# ECE411_Project1.net
KiCad netlist of a schematic drawn in EAGLE
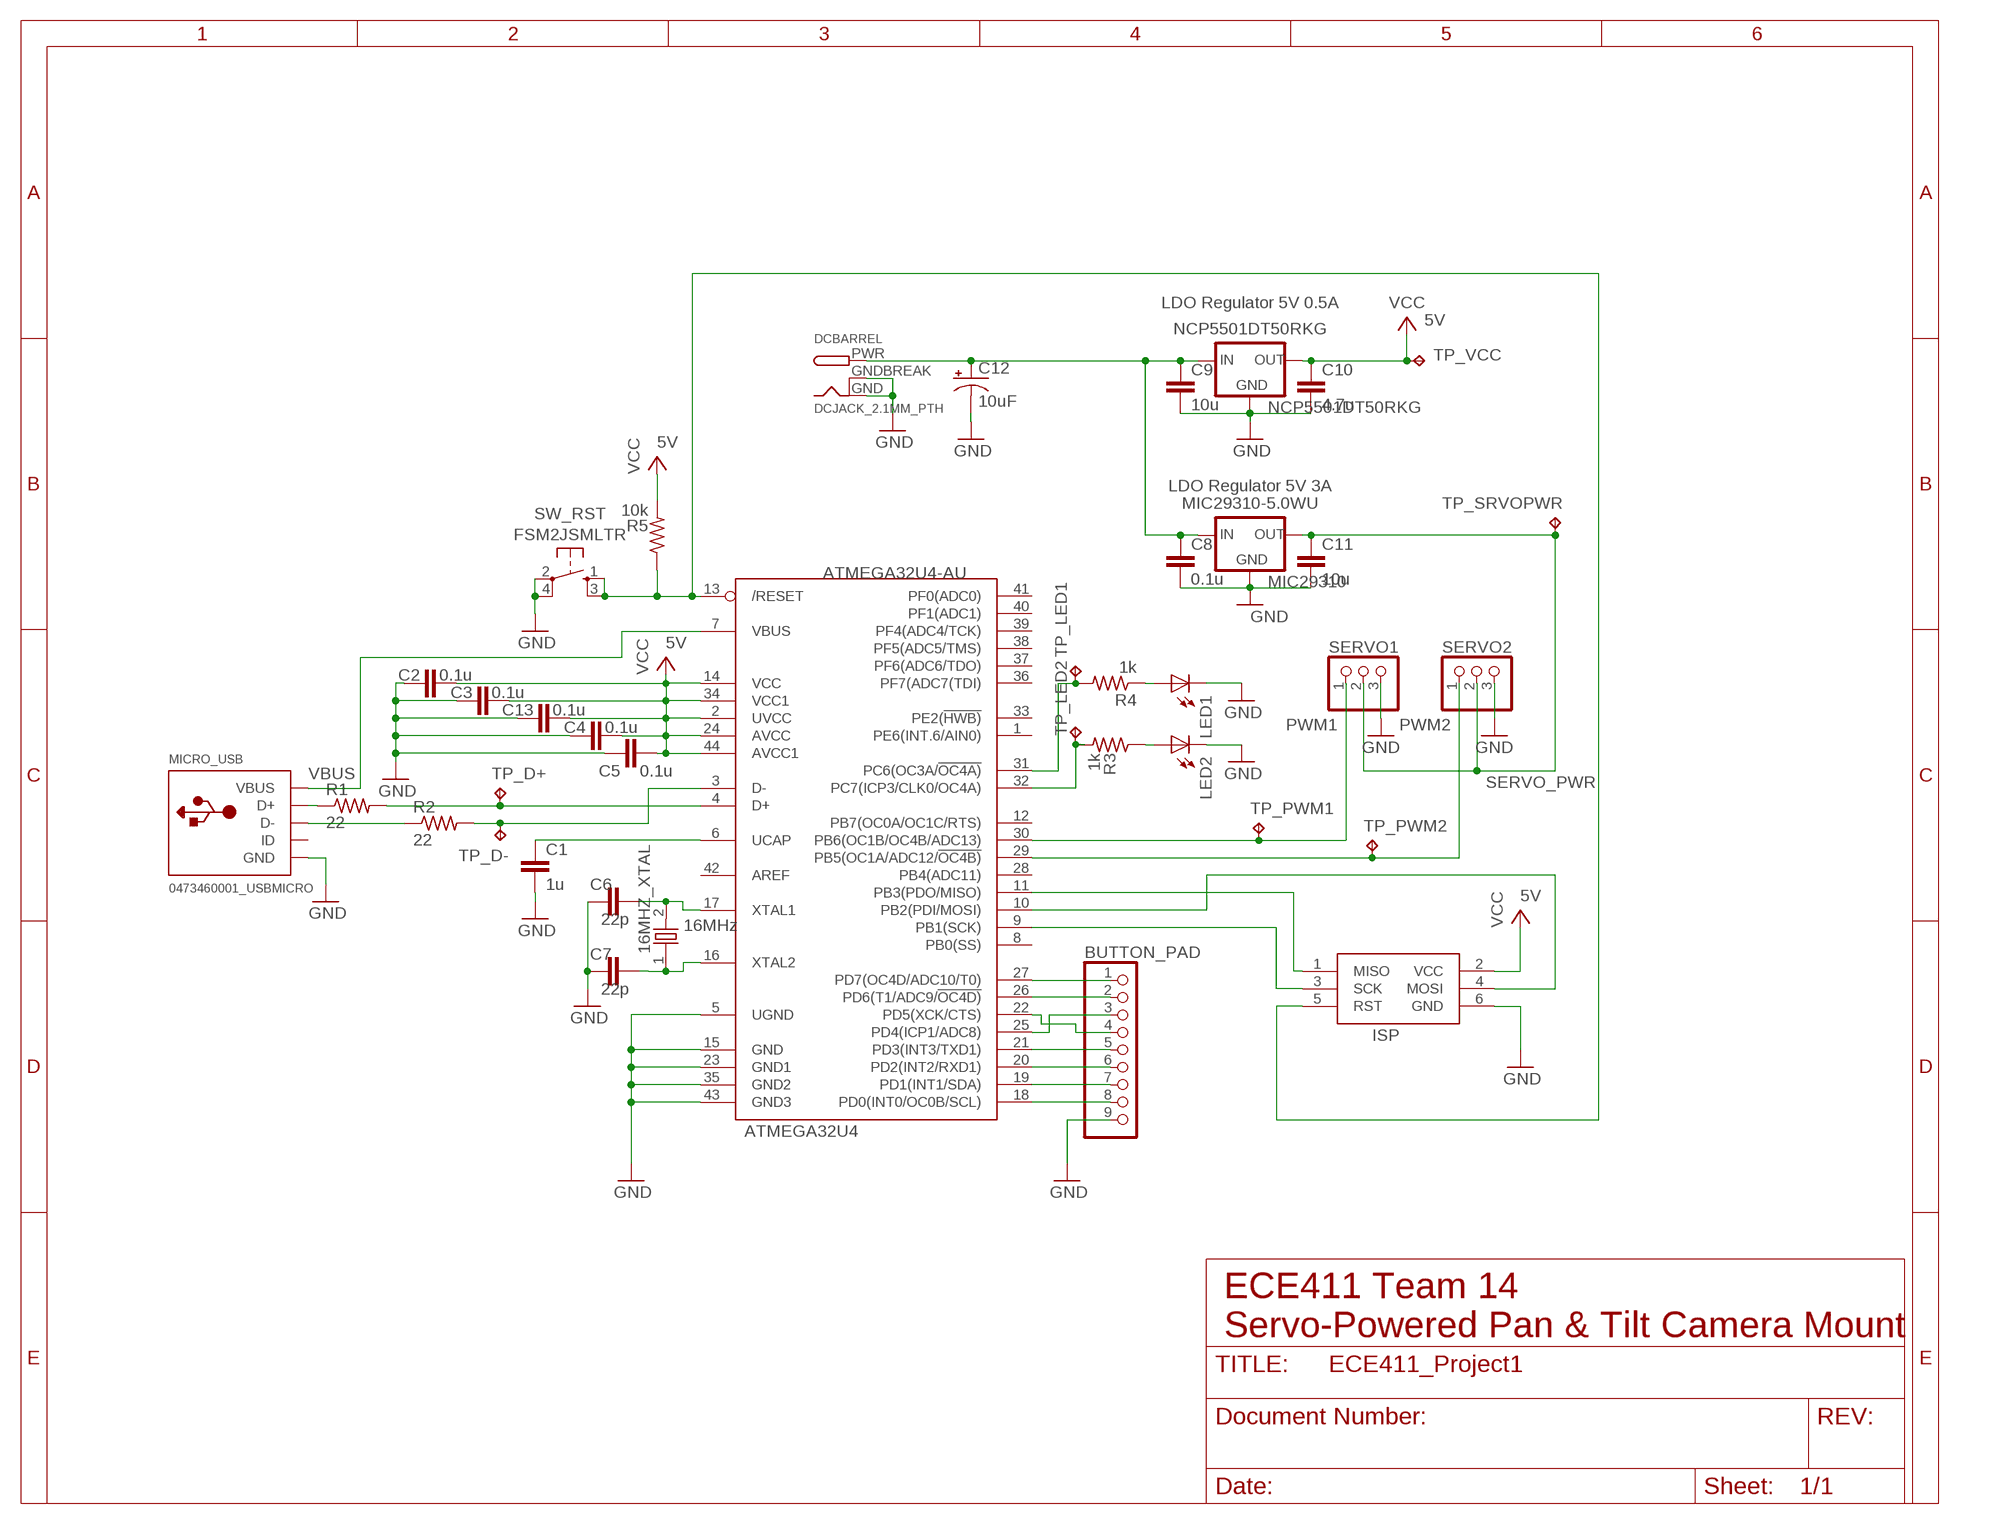
[diagram p0: schematic, sheet 1]

(export (version "E")
  (design (tool "Eeschema 10.0.6"))
  (components
    (comp (ref "16MHZ_XTAL")
      (value "16MHz")
      (footprint "eagle-import:ATS160SM-1")
      (libsource (lib "eagle-import") (part "ATS160SM-1"))
    )
    (comp (ref "ATMEGA32U4")
      (value "ATMEGA32U4-AU")
      (footprint "eagle-import:TQFP44")
      (libsource (lib "eagle-import") (part "ATMEGA32U4-AU"))
    )
    (comp (ref "BUTTON_PAD")
      (value "PINHD-1X9")
      (footprint "eagle-import:1X09")
      (libsource (lib "eagle-import") (part "PINHD-1X9"))
    )
    (comp (ref "C1")
      (value "1u")
      (footprint "eagle-import:C1206")
      (libsource (lib "eagle-import") (part "C-EUC1206"))
    )
    (comp (ref "C2")
      (value "0.1u")
      (footprint "eagle-import:C1206")
      (libsource (lib "eagle-import") (part "C-EUC1206"))
    )
    (comp (ref "C3")
      (value "0.1u")
      (footprint "eagle-import:C1206")
      (libsource (lib "eagle-import") (part "C-EUC1206"))
    )
    (comp (ref "C4")
      (value "0.1u")
      (footprint "eagle-import:C1206")
      (libsource (lib "eagle-import") (part "C-EUC1206"))
    )
    (comp (ref "C5")
      (value "0.1u")
      (footprint "eagle-import:C1206")
      (libsource (lib "eagle-import") (part "C-EUC1206"))
    )
    (comp (ref "C6")
      (value "22p")
      (footprint "eagle-import:C0805")
      (libsource (lib "eagle-import") (part "C-EUC0805"))
    )
    (comp (ref "C7")
      (value "22p")
      (footprint "eagle-import:C0805")
      (libsource (lib "eagle-import") (part "C-EUC0805"))
    )
    (comp (ref "C8")
      (value "0.1u")
      (footprint "eagle-import:C1206")
      (libsource (lib "eagle-import") (part "C-EUC1206"))
    )
    (comp (ref "C9")
      (value "10u")
      (footprint "eagle-import:C1206")
      (libsource (lib "eagle-import") (part "C-EUC1206"))
    )
    (comp (ref "C10")
      (value "4.7u")
      (footprint "eagle-import:C1206")
      (libsource (lib "eagle-import") (part "C-EUC1206"))
    )
    (comp (ref "C11")
      (value "10u")
      (footprint "eagle-import:C1206")
      (libsource (lib "eagle-import") (part "C-EUC1206"))
    )
    (comp (ref "C12")
      (value "10uF")
      (footprint "eagle-import:UD-5X5,4_NICHICON")
      (libsource (lib "eagle-import") (part "UWT1V100MCL1GB"))
    )
    (comp (ref "C13")
      (value "0.1u")
      (footprint "eagle-import:C1206")
      (libsource (lib "eagle-import") (part "C-EUC1206"))
    )
    (comp (ref "DCBARREL")
      (value "DCJACK_2.1MM_PTH")
      (footprint "eagle-import:DCJACK_2.1MM_PTH")
      (libsource (lib "eagle-import") (part "DCJACK_2.1MM_PTH"))
    )
    (comp (ref "ISP")
      (value "AVRISP-6")
      (footprint "eagle-import:AVRISP")
      (libsource (lib "eagle-import") (part "AVRISP-6"))
    )
    (comp (ref "LED1")
      (value "LEDSMT1206")
      (footprint "eagle-import:1206")
      (libsource (lib "eagle-import") (part "LEDSMT1206"))
    )
    (comp (ref "LED2")
      (value "LEDSMT1206")
      (footprint "eagle-import:1206")
      (libsource (lib "eagle-import") (part "LEDSMT1206"))
    )
    (comp (ref "MIC29310")
      (value "MIC29310-5.0WU")
      (footprint "eagle-import:TO-263_D2PAK")
      (libsource (lib "eagle-import") (part "MIC29310-5.0WU"))
    )
    (comp (ref "MICRO_USB")
      (value "0473460001_USBMICRO")
      (footprint "eagle-import:MOLEX_USBMICRO")
      (libsource (lib "eagle-import") (part "0473460001_USBMICRO"))
    )
    (comp (ref "NCP5501DT50RKG")
      (value "NCP5501DT50RKG")
      (footprint "eagle-import:TO-263_D2PAK")
      (libsource (lib "eagle-import") (part "NCP5501DT50RKG"))
    )
    (comp (ref "R1")
      (value "22")
      (footprint "eagle-import:R1206")
      (libsource (lib "eagle-import") (part "R-US_R1206"))
    )
    (comp (ref "R2")
      (value "22")
      (footprint "eagle-import:R1206")
      (libsource (lib "eagle-import") (part "R-US_R1206"))
    )
    (comp (ref "R3")
      (value "1k")
      (footprint "eagle-import:R1206")
      (libsource (lib "eagle-import") (part "R-US_R1206"))
    )
    (comp (ref "R4")
      (value "1k")
      (footprint "eagle-import:R1206")
      (libsource (lib "eagle-import") (part "R-US_R1206"))
    )
    (comp (ref "R5")
      (value "10k")
      (footprint "eagle-import:R1206")
      (libsource (lib "eagle-import") (part "R-US_R1206"))
    )
    (comp (ref "SERVO1")
      (value "PINHD-1X3")
      (footprint "eagle-import:1X03")
      (libsource (lib "eagle-import") (part "PINHD-1X3"))
    )
    (comp (ref "SERVO2")
      (value "PINHD-1X3")
      (footprint "eagle-import:1X03")
      (libsource (lib "eagle-import") (part "PINHD-1X3"))
    )
    (comp (ref "SW_RST")
      (value "FSM2JSMLTR")
      (footprint "eagle-import:FSM2JSMLTR")
      (libsource (lib "eagle-import") (part "FSM2JSMLTR"))
    )
    (comp (ref "TP_D+")
      (value "TPTP20SQ")
      (footprint "eagle-import:TP20SQ")
      (libsource (lib "eagle-import") (part "TPTP20SQ"))
    )
    (comp (ref "TP_D-")
      (value "TPTP20SQ")
      (footprint "eagle-import:TP20SQ")
      (libsource (lib "eagle-import") (part "TPTP20SQ"))
    )
    (comp (ref "TP_LED1")
      (value "TPTP20SQ")
      (footprint "eagle-import:TP20SQ")
      (libsource (lib "eagle-import") (part "TPTP20SQ"))
    )
    (comp (ref "TP_LED2")
      (value "TPTP20SQ")
      (footprint "eagle-import:TP20SQ")
      (libsource (lib "eagle-import") (part "TPTP20SQ"))
    )
    (comp (ref "TP_PWM1")
      (value "TPTP20SQ")
      (footprint "eagle-import:TP20SQ")
      (libsource (lib "eagle-import") (part "TPTP20SQ"))
    )
    (comp (ref "TP_PWM2")
      (value "TPTP20SQ")
      (footprint "eagle-import:TP20SQ")
      (libsource (lib "eagle-import") (part "TPTP20SQ"))
    )
    (comp (ref "TP_SRVOPWR")
      (value "TPTP20SQ")
      (footprint "eagle-import:TP20SQ")
      (libsource (lib "eagle-import") (part "TPTP20SQ"))
    )
    (comp (ref "TP_VCC")
      (value "TPTP20SQ")
      (footprint "eagle-import:TP20SQ")
      (libsource (lib "eagle-import") (part "TPTP20SQ"))
    )
  )
  (nets
    (net (code "1") (name "/PWM1") (class "Default")
      (node (ref "ATMEGA32U4") (pin "30") (pinfunction "PB6(OC1B/OC4B/ADC13)_30") (pintype "bidirectional"))
      (node (ref "SERVO1") (pin "1") (pinfunction "1_1") (pintype "passive"))
      (node (ref "TP_PWM1") (pin "TP") (pinfunction "TP_TP") (pintype "input"))
    )
    (net (code "2") (name "/PWM2") (class "Default")
      (node (ref "ATMEGA32U4") (pin "29") (pinfunction "PB5(OC1A/ADC12/~{OC4B})_29") (pintype "bidirectional"))
      (node (ref "SERVO2") (pin "1") (pinfunction "1_1") (pintype "passive"))
      (node (ref "TP_PWM2") (pin "TP") (pinfunction "TP_TP") (pintype "input"))
    )
    (net (code "3") (name "/SERVO_PWR") (class "Default")
      (node (ref "C11") (pin "1") (pinfunction "1_1") (pintype "passive"))
      (node (ref "MIC29310") (pin "3") (pinfunction "OUT_3") (pintype "passive"))
      (node (ref "SERVO1") (pin "2") (pinfunction "2_2") (pintype "passive"))
      (node (ref "SERVO2") (pin "2") (pinfunction "2_2") (pintype "passive"))
      (node (ref "TP_SRVOPWR") (pin "TP") (pinfunction "TP_TP") (pintype "input"))
    )
    (net (code "4") (name "/VBUS") (class "Default")
      (node (ref "ATMEGA32U4") (pin "7") (pinfunction "VBUS_7") (pintype "bidirectional"))
      (node (ref "MICRO_USB") (pin "1") (pinfunction "VBUS_1") (pintype "power_in"))
    )
    (net (code "5") (name "GND") (class "Default")
      (node (ref "ATMEGA32U4") (pin "15") (pinfunction "GND_15") (pintype "bidirectional"))
      (node (ref "ATMEGA32U4") (pin "23") (pinfunction "GND1_23") (pintype "bidirectional"))
      (node (ref "ATMEGA32U4") (pin "35") (pinfunction "GND2_35") (pintype "bidirectional"))
      (node (ref "ATMEGA32U4") (pin "43") (pinfunction "GND3_43") (pintype "bidirectional"))
      (node (ref "ATMEGA32U4") (pin "5") (pinfunction "UGND_5") (pintype "bidirectional"))
      (node (ref "BUTTON_PAD") (pin "9") (pinfunction "9_9") (pintype "passive"))
      (node (ref "C1") (pin "2") (pinfunction "2_2") (pintype "passive"))
      (node (ref "C10") (pin "2") (pinfunction "2_2") (pintype "passive"))
      (node (ref "C11") (pin "2") (pinfunction "2_2") (pintype "passive"))
      (node (ref "C12") (pin "-") (pinfunction "-_-") (pintype "passive"))
      (node (ref "C13") (pin "1") (pinfunction "1_1") (pintype "passive"))
      (node (ref "C2") (pin "1") (pinfunction "1_1") (pintype "passive"))
      (node (ref "C3") (pin "1") (pinfunction "1_1") (pintype "passive"))
      (node (ref "C4") (pin "1") (pinfunction "1_1") (pintype "passive"))
      (node (ref "C5") (pin "1") (pinfunction "1_1") (pintype "passive"))
      (node (ref "C6") (pin "1") (pinfunction "1_1") (pintype "passive"))
      (node (ref "C7") (pin "1") (pinfunction "1_1") (pintype "passive"))
      (node (ref "C8") (pin "2") (pinfunction "2_2") (pintype "passive"))
      (node (ref "C9") (pin "2") (pinfunction "2_2") (pintype "passive"))
      (node (ref "DCBARREL") (pin "GND") (pinfunction "GND_GND") (pintype "power_in"))
      (node (ref "DCBARREL") (pin "GNDBREAK") (pinfunction "GNDBREAK_GNDBREAK") (pintype "power_in"))
      (node (ref "ISP") (pin "6") (pinfunction "GND_6") (pintype "power_in"))
      (node (ref "LED1") (pin "C") (pinfunction "C_C") (pintype "passive"))
      (node (ref "LED2") (pin "C") (pinfunction "C_C") (pintype "passive"))
      (node (ref "MIC29310") (pin "2") (pinfunction "GND_2") (pintype "input"))
      (node (ref "MICRO_USB") (pin "5") (pinfunction "GND_5") (pintype "power_in"))
      (node (ref "MICRO_USB") (pin "G1") (pinfunction "GND_G1") (pintype "power_in"))
      (node (ref "MICRO_USB") (pin "G2") (pinfunction "GND_G2") (pintype "power_in"))
      (node (ref "MICRO_USB") (pin "G3") (pinfunction "GND_G3") (pintype "power_in"))
      (node (ref "MICRO_USB") (pin "G4") (pinfunction "GND_G4") (pintype "power_in"))
      (node (ref "MICRO_USB") (pin "G5") (pinfunction "GND_G5") (pintype "power_in"))
      (node (ref "MICRO_USB") (pin "G6") (pinfunction "GND_G6") (pintype "power_in"))
      (node (ref "NCP5501DT50RKG") (pin "2") (pinfunction "GND_2") (pintype "input"))
      (node (ref "SERVO1") (pin "3") (pinfunction "3_3") (pintype "passive"))
      (node (ref "SERVO2") (pin "3") (pinfunction "3_3") (pintype "passive"))
      (node (ref "SW_RST") (pin "2") (pinfunction "2_2") (pintype "passive"))
      (node (ref "SW_RST") (pin "4") (pinfunction "4_4") (pintype "passive"))
    )
    (net (code "6") (name "Net-(ATMEGA32U4-D+)") (class "Default")
      (node (ref "ATMEGA32U4") (pin "4") (pinfunction "D+_4") (pintype "bidirectional"))
      (node (ref "R1") (pin "2") (pinfunction "2_2") (pintype "passive"))
      (node (ref "TP_D+") (pin "TP") (pinfunction "TP_TP") (pintype "input"))
    )
    (net (code "7") (name "Net-(ATMEGA32U4-D-)") (class "Default")
      (node (ref "ATMEGA32U4") (pin "3") (pinfunction "D-_3") (pintype "bidirectional"))
      (node (ref "R2") (pin "2") (pinfunction "2_2") (pintype "passive"))
      (node (ref "TP_D-") (pin "TP") (pinfunction "TP_TP") (pintype "input"))
    )
    (net (code "8") (name "Net-(ATMEGA32U4-PB1(SCK))") (class "Default")
      (node (ref "ATMEGA32U4") (pin "9") (pinfunction "PB1(SCK)_9") (pintype "bidirectional"))
      (node (ref "ISP") (pin "3") (pinfunction "SCK_3") (pintype "output"))
    )
    (net (code "9") (name "Net-(ATMEGA32U4-PB2(PDI{slash}MOSI))") (class "Default")
      (node (ref "ATMEGA32U4") (pin "10") (pinfunction "PB2(PDI/MOSI)_10") (pintype "bidirectional"))
      (node (ref "ISP") (pin "4") (pinfunction "MOSI_4") (pintype "output"))
    )
    (net (code "10") (name "Net-(ATMEGA32U4-PB3(PDO{slash}MISO))") (class "Default")
      (node (ref "ATMEGA32U4") (pin "11") (pinfunction "PB3(PDO/MISO)_11") (pintype "bidirectional"))
      (node (ref "ISP") (pin "1") (pinfunction "MISO_1") (pintype "input"))
    )
    (net (code "11") (name "Net-(ATMEGA32U4-PC6(OC3A{slash}~{OC4A}))") (class "Default")
      (node (ref "ATMEGA32U4") (pin "31") (pinfunction "PC6(OC3A/~{OC4A})_31") (pintype "bidirectional"))
      (node (ref "R4") (pin "2") (pinfunction "2_2") (pintype "passive"))
      (node (ref "TP_LED1") (pin "TP") (pinfunction "TP_TP") (pintype "input"))
    )
    (net (code "12") (name "Net-(ATMEGA32U4-PC7(ICP3{slash}CLK0{slash}OC4A))") (class "Default")
      (node (ref "ATMEGA32U4") (pin "32") (pinfunction "PC7(ICP3/CLK0/OC4A)_32") (pintype "bidirectional"))
      (node (ref "R3") (pin "2") (pinfunction "2_2") (pintype "passive"))
      (node (ref "TP_LED2") (pin "TP") (pinfunction "TP_TP") (pintype "input"))
    )
    (net (code "13") (name "Net-(ATMEGA32U4-PD0(INT0{slash}OC0B{slash}SCL))") (class "Default")
      (node (ref "ATMEGA32U4") (pin "18") (pinfunction "PD0(INT0/OC0B/SCL)_18") (pintype "bidirectional"))
      (node (ref "BUTTON_PAD") (pin "8") (pinfunction "8_8") (pintype "passive"))
    )
    (net (code "14") (name "Net-(ATMEGA32U4-PD1(INT1{slash}SDA))") (class "Default")
      (node (ref "ATMEGA32U4") (pin "19") (pinfunction "PD1(INT1/SDA)_19") (pintype "bidirectional"))
      (node (ref "BUTTON_PAD") (pin "7") (pinfunction "7_7") (pintype "passive"))
    )
    (net (code "15") (name "Net-(ATMEGA32U4-PD2(INT2{slash}RXD1))") (class "Default")
      (node (ref "ATMEGA32U4") (pin "20") (pinfunction "PD2(INT2/RXD1)_20") (pintype "bidirectional"))
      (node (ref "BUTTON_PAD") (pin "6") (pinfunction "6_6") (pintype "passive"))
    )
    (net (code "16") (name "Net-(ATMEGA32U4-PD3(INT3{slash}TXD1))") (class "Default")
      (node (ref "ATMEGA32U4") (pin "21") (pinfunction "PD3(INT3/TXD1)_21") (pintype "bidirectional"))
      (node (ref "BUTTON_PAD") (pin "5") (pinfunction "5_5") (pintype "passive"))
    )
    (net (code "17") (name "Net-(ATMEGA32U4-PD4(ICP1{slash}ADC8))") (class "Default")
      (node (ref "ATMEGA32U4") (pin "25") (pinfunction "PD4(ICP1/ADC8)_25") (pintype "bidirectional"))
      (node (ref "BUTTON_PAD") (pin "3") (pinfunction "3_3") (pintype "passive"))
    )
    (net (code "18") (name "Net-(ATMEGA32U4-PD5(XCK{slash}CTS))") (class "Default")
      (node (ref "ATMEGA32U4") (pin "22") (pinfunction "PD5(XCK/CTS)_22") (pintype "bidirectional"))
      (node (ref "BUTTON_PAD") (pin "4") (pinfunction "4_4") (pintype "passive"))
    )
    (net (code "19") (name "Net-(ATMEGA32U4-PD6(T1{slash}ADC9{slash}~{OC4D}))") (class "Default")
      (node (ref "ATMEGA32U4") (pin "26") (pinfunction "PD6(T1/ADC9/~{OC4D})_26") (pintype "bidirectional"))
      (node (ref "BUTTON_PAD") (pin "2") (pinfunction "2_2") (pintype "passive"))
    )
    (net (code "20") (name "Net-(ATMEGA32U4-PD7(OC4D{slash}ADC10{slash}T0))") (class "Default")
      (node (ref "ATMEGA32U4") (pin "27") (pinfunction "PD7(OC4D/ADC10/T0)_27") (pintype "bidirectional"))
      (node (ref "BUTTON_PAD") (pin "1") (pinfunction "1_1") (pintype "passive"))
    )
    (net (code "21") (name "Net-(ATMEGA32U4-UCAP)") (class "Default")
      (node (ref "ATMEGA32U4") (pin "6") (pinfunction "UCAP_6") (pintype "bidirectional"))
      (node (ref "C1") (pin "1") (pinfunction "1_1") (pintype "passive"))
    )
    (net (code "22") (name "Net-(ATMEGA32U4-XTAL1)") (class "Default")
      (node (ref "16MHZ_XTAL") (pin "2") (pinfunction "2_2") (pintype "passive"))
      (node (ref "ATMEGA32U4") (pin "17") (pinfunction "XTAL1_17") (pintype "bidirectional"))
      (node (ref "C6") (pin "2") (pinfunction "2_2") (pintype "passive"))
    )
    (net (code "23") (name "Net-(ATMEGA32U4-XTAL2)") (class "Default")
      (node (ref "16MHZ_XTAL") (pin "1") (pinfunction "1_1") (pintype "passive"))
      (node (ref "ATMEGA32U4") (pin "16") (pinfunction "XTAL2_16") (pintype "bidirectional"))
      (node (ref "C7") (pin "2") (pinfunction "2_2") (pintype "passive"))
    )
    (net (code "24") (name "Net-(ATMEGA32U4-{slash}RESET)") (class "Default")
      (node (ref "ATMEGA32U4") (pin "13") (pinfunction "/RESET_13") (pintype "bidirectional"))
      (node (ref "ISP") (pin "5") (pinfunction "RST_5") (pintype "output"))
      (node (ref "R5") (pin "1") (pinfunction "1_1") (pintype "passive"))
      (node (ref "SW_RST") (pin "1") (pinfunction "1_1") (pintype "passive"))
      (node (ref "SW_RST") (pin "3") (pinfunction "3_3") (pintype "passive"))
    )
    (net (code "25") (name "Net-(LED1-PadA)") (class "Default")
      (node (ref "LED1") (pin "A") (pinfunction "A_A") (pintype "passive"))
      (node (ref "R4") (pin "1") (pinfunction "1_1") (pintype "passive"))
    )
    (net (code "26") (name "Net-(LED2-PadA)") (class "Default")
      (node (ref "LED2") (pin "A") (pinfunction "A_A") (pintype "passive"))
      (node (ref "R3") (pin "1") (pinfunction "1_1") (pintype "passive"))
    )
    (net (code "27") (name "Net-(MIC29310-IN)") (class "Default")
      (node (ref "C12") (pin "+") (pinfunction "+_+") (pintype "passive"))
      (node (ref "C8") (pin "1") (pinfunction "1_1") (pintype "passive"))
      (node (ref "C9") (pin "1") (pinfunction "1_1") (pintype "passive"))
      (node (ref "DCBARREL") (pin "PWR") (pinfunction "PWR_PWR") (pintype "power_in"))
      (node (ref "MIC29310") (pin "1") (pinfunction "IN_1") (pintype "input"))
      (node (ref "NCP5501DT50RKG") (pin "1") (pinfunction "IN_1") (pintype "input"))
    )
    (net (code "28") (name "Net-(MICRO_USB-D+)") (class "Default")
      (node (ref "MICRO_USB") (pin "3") (pinfunction "D+_3") (pintype "bidirectional"))
      (node (ref "R1") (pin "1") (pinfunction "1_1") (pintype "passive"))
    )
    (net (code "29") (name "Net-(MICRO_USB-D-)") (class "Default")
      (node (ref "MICRO_USB") (pin "2") (pinfunction "D-_2") (pintype "bidirectional"))
      (node (ref "R2") (pin "1") (pinfunction "1_1") (pintype "passive"))
    )
    (net (code "30") (name "VCC") (class "Default")
      (node (ref "ATMEGA32U4") (pin "14") (pinfunction "VCC_14") (pintype "bidirectional"))
      (node (ref "ATMEGA32U4") (pin "2") (pinfunction "UVCC_2") (pintype "bidirectional"))
      (node (ref "ATMEGA32U4") (pin "24") (pinfunction "AVCC_24") (pintype "bidirectional"))
      (node (ref "ATMEGA32U4") (pin "34") (pinfunction "VCC1_34") (pintype "bidirectional"))
      (node (ref "ATMEGA32U4") (pin "44") (pinfunction "AVCC1_44") (pintype "bidirectional"))
      (node (ref "C10") (pin "1") (pinfunction "1_1") (pintype "passive"))
      (node (ref "C13") (pin "2") (pinfunction "2_2") (pintype "passive"))
      (node (ref "C2") (pin "2") (pinfunction "2_2") (pintype "passive"))
      (node (ref "C3") (pin "2") (pinfunction "2_2") (pintype "passive"))
      (node (ref "C4") (pin "2") (pinfunction "2_2") (pintype "passive"))
      (node (ref "C5") (pin "2") (pinfunction "2_2") (pintype "passive"))
      (node (ref "ISP") (pin "2") (pinfunction "VCC_2") (pintype "power_in"))
      (node (ref "NCP5501DT50RKG") (pin "3") (pinfunction "OUT_3") (pintype "passive"))
      (node (ref "R5") (pin "2") (pinfunction "2_2") (pintype "passive"))
      (node (ref "TP_VCC") (pin "TP") (pinfunction "TP_TP") (pintype "input"))
    )
    (net (code "31") (name "unconnected-(ATMEGA32U4-AREF-Pad42)") (class "Default")
      (node (ref "ATMEGA32U4") (pin "42") (pinfunction "AREF_42") (pintype "bidirectional"))
    )
    (net (code "32") (name "unconnected-(ATMEGA32U4-PB0(SS)-Pad8)") (class "Default")
      (node (ref "ATMEGA32U4") (pin "8") (pinfunction "PB0(SS)_8") (pintype "bidirectional"))
    )
    (net (code "33") (name "unconnected-(ATMEGA32U4-PB4(ADC11)-Pad28)") (class "Default")
      (node (ref "ATMEGA32U4") (pin "28") (pinfunction "PB4(ADC11)_28") (pintype "bidirectional"))
    )
    (net (code "34") (name "unconnected-(ATMEGA32U4-PB7(OC0A{slash}OC1C{slash}RTS)-Pad12)") (class "Default")
      (node (ref "ATMEGA32U4") (pin "12") (pinfunction "PB7(OC0A/OC1C/RTS)_12") (pintype "bidirectional"))
    )
    (net (code "35") (name "unconnected-(ATMEGA32U4-PE2(~{HWB})-Pad33)") (class "Default")
      (node (ref "ATMEGA32U4") (pin "33") (pinfunction "PE2(~{HWB})_33") (pintype "bidirectional"))
    )
    (net (code "36") (name "unconnected-(ATMEGA32U4-PE6(INT.6{slash}AIN0)-Pad1)") (class "Default")
      (node (ref "ATMEGA32U4") (pin "1") (pinfunction "PE6(INT.6/AIN0)_1") (pintype "bidirectional"))
    )
    (net (code "37") (name "unconnected-(ATMEGA32U4-PF0(ADC0)-Pad41)") (class "Default")
      (node (ref "ATMEGA32U4") (pin "41") (pinfunction "PF0(ADC0)_41") (pintype "bidirectional"))
    )
    (net (code "38") (name "unconnected-(ATMEGA32U4-PF1(ADC1)-Pad40)") (class "Default")
      (node (ref "ATMEGA32U4") (pin "40") (pinfunction "PF1(ADC1)_40") (pintype "bidirectional"))
    )
    (net (code "39") (name "unconnected-(ATMEGA32U4-PF4(ADC4{slash}TCK)-Pad39)") (class "Default")
      (node (ref "ATMEGA32U4") (pin "39") (pinfunction "PF4(ADC4/TCK)_39") (pintype "bidirectional"))
    )
    (net (code "40") (name "unconnected-(ATMEGA32U4-PF5(ADC5{slash}TMS)-Pad38)") (class "Default")
      (node (ref "ATMEGA32U4") (pin "38") (pinfunction "PF5(ADC5/TMS)_38") (pintype "bidirectional"))
    )
    (net (code "41") (name "unconnected-(ATMEGA32U4-PF6(ADC6{slash}TDO)-Pad37)") (class "Default")
      (node (ref "ATMEGA32U4") (pin "37") (pinfunction "PF6(ADC6/TDO)_37") (pintype "bidirectional"))
    )
    (net (code "42") (name "unconnected-(ATMEGA32U4-PF7(ADC7(TDI)-Pad36)") (class "Default")
      (node (ref "ATMEGA32U4") (pin "36") (pinfunction "PF7(ADC7(TDI)_36") (pintype "bidirectional"))
    )
    (net (code "43") (name "unconnected-(MICRO_USB-ID-Pad4)") (class "Default")
      (node (ref "MICRO_USB") (pin "4") (pinfunction "ID_4") (pintype "bidirectional"))
    )
  )
)
